# ArduinoNanoShield.net
KiCad netlist of a schematic drawn in Altium Designer
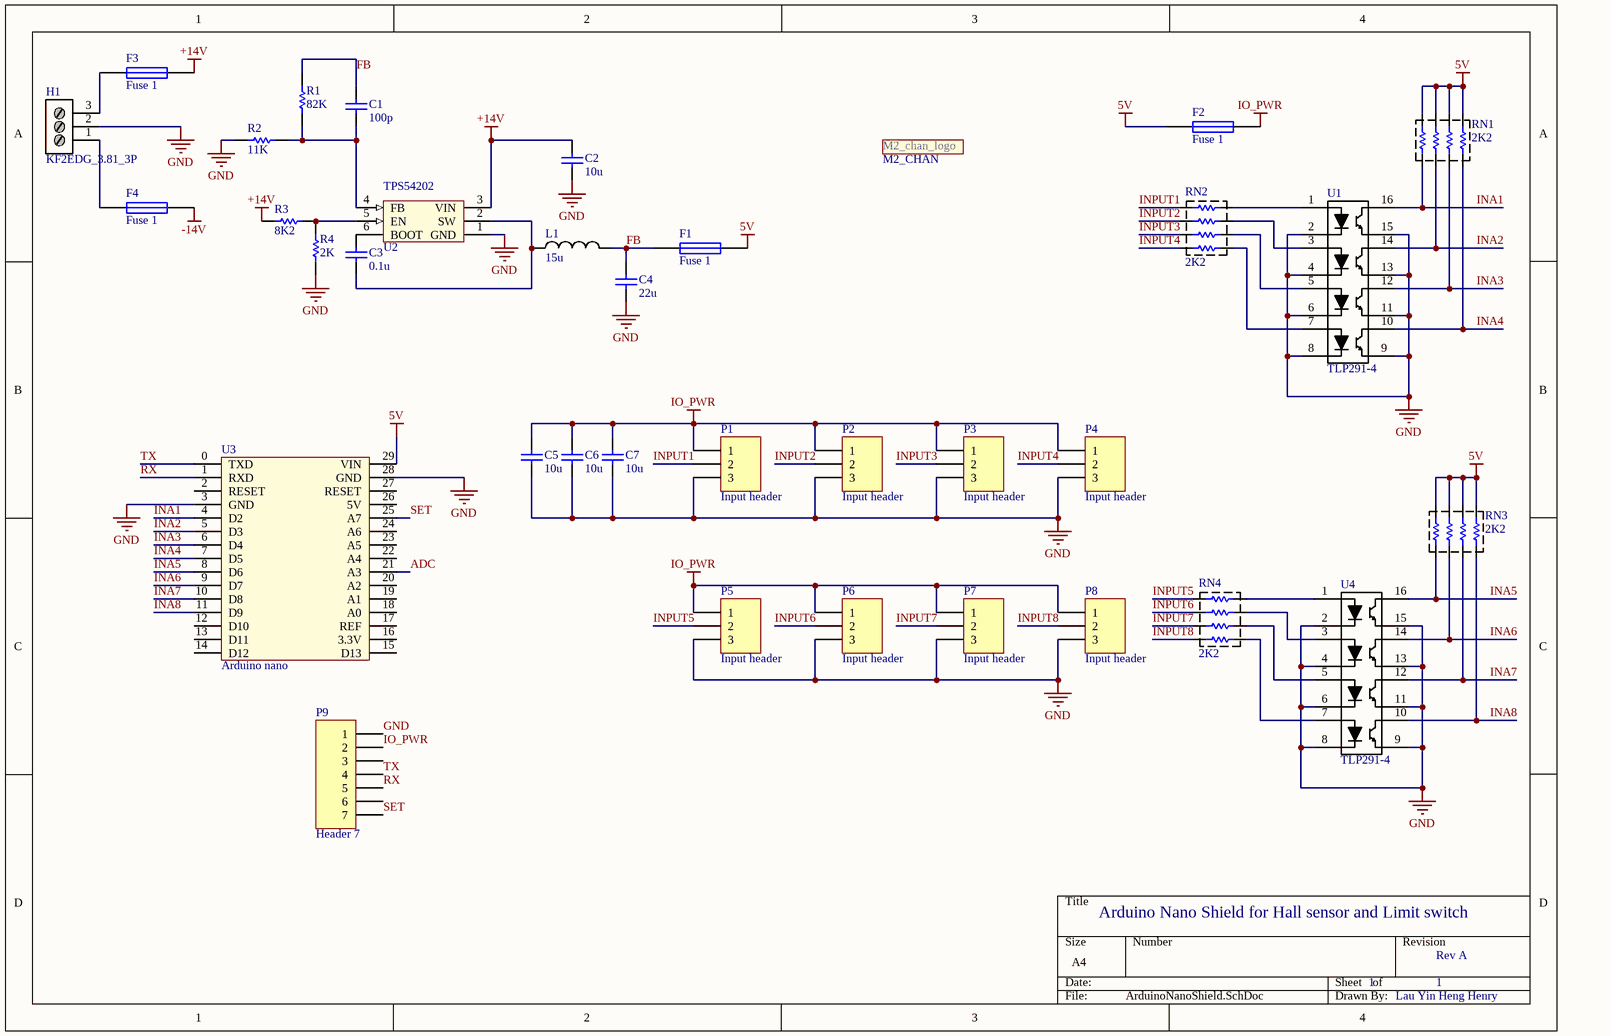
[diagram p0: ArduinoNanoShield.SchDoc]

(export (version "E")
  (design (tool "Eeschema 10.0.6"))
  (components
    (comp (ref "C1")
      (value "100p")
      (footprint "CAPC1608X90N")
      (description "Capacitor")
      (fields (field (name "Comment") "Cap") (field (name "PUBLISHER") "Altium Limited"))
      (libsource (lib "IOBoard_Low") (part "Cap"))
    )
    (comp (ref "C2")
      (value "10u")
      (footprint "CAPC2012X135N")
      (description "Capacitor")
      (fields (field (name "Comment") "Cap") (field (name "PUBLISHER") "Altium Limited"))
      (libsource (lib "IOBoard_Low") (part "Cap"))
    )
    (comp (ref "C3")
      (value "0.1u")
      (footprint "CAPC1608X90N")
      (description "Capacitor")
      (fields (field (name "Comment") "Cap") (field (name "PUBLISHER") "Altium Limited"))
      (libsource (lib "IOBoard_Low") (part "Cap"))
    )
    (comp (ref "C4")
      (value "22u")
      (footprint "CAPC2012X135N")
      (description "Capacitor")
      (fields (field (name "Comment") "Cap") (field (name "PUBLISHER") "Altium Limited"))
      (libsource (lib "IOBoard_Low") (part "Cap"))
    )
    (comp (ref "C5")
      (value "10u")
      (footprint "CAPC2012X135N")
      (description "Capacitor")
      (fields (field (name "Comment") "Cap") (field (name "PUBLISHER") "Altium Limited"))
      (libsource (lib "IOBoard_Low") (part "Cap"))
    )
    (comp (ref "C6")
      (value "10u")
      (footprint "CAPC2012X135N")
      (description "Capacitor")
      (fields (field (name "Comment") "Cap") (field (name "PUBLISHER") "Altium Limited"))
      (libsource (lib "IOBoard_Low") (part "Cap"))
    )
    (comp (ref "C7")
      (value "10u")
      (footprint "CAPC2012X135N")
      (description "Capacitor")
      (fields (field (name "Comment") "Cap") (field (name "PUBLISHER") "Altium Limited"))
      (libsource (lib "IOBoard_Low") (part "Cap"))
    )
    (comp (ref "F1")
      (value "Fuse 1")
      (footprint "FUSE_1808")
      (description "Fuse")
      (fields (field (name "PUBLISHER") "Altium Limited"))
      (libsource (lib "Miscellaneous Devices") (part "Fuse 1"))
    )
    (comp (ref "F2")
      (value "Fuse 1")
      (footprint "FUSE_1808")
      (description "Fuse")
      (fields (field (name "PUBLISHER") "Altium Limited"))
      (libsource (lib "Miscellaneous Devices") (part "Fuse 1"))
    )
    (comp (ref "F3")
      (value "Fuse 1")
      (footprint "FUSE_1808")
      (description "Fuse")
      (fields (field (name "PUBLISHER") "Altium Limited"))
      (libsource (lib "Miscellaneous Devices") (part "Fuse 1"))
    )
    (comp (ref "F4")
      (value "Fuse 1")
      (footprint "FUSE_1808")
      (description "Fuse")
      (fields (field (name "PUBLISHER") "Altium Limited"))
      (libsource (lib "Miscellaneous Devices") (part "Fuse 1"))
    )
    (comp (ref "H1")
      (value "KF2EDG_3.81_3P")
      (footprint "KF2EDG_3.81_RA_3P")
      (description "KF2EDG_3.81_3P screw terminal connect, must be mount at the edge of the PCB")
      (libsource (lib "IOBoard_Low") (part "KF2EDG_3.81_3P"))
    )
    (comp (ref "L1")
      (value "15u")
      (footprint "INDC_5.5x5.3x3")
      (description "15uH inductor with 2A saturation current. Dimension is 5.5 * 5.2 * 3 mm^3")
      (fields (field (name "Comment") "15uH inductor"))
      (libsource (lib "IOBoard_Low") (part "INDC_MPX1D0530L150"))
    )
    (comp (ref "M2_CHAN")
      (value "M2_CHAN")
      (footprint "M2_chan_thin")
      (libsource (lib "IOBoard_Low") (part "M2_CHAN"))
    )
    (comp (ref "P1")
      (value "Input header")
      (footprint "HDR1X3")
      (description "Header, 3-Pin")
      (fields (field (name "PUBLISHER") "Altium Limited"))
      (libsource (lib "Miscellaneous Connectors") (part "Header 3"))
    )
    (comp (ref "P2")
      (value "Input header")
      (footprint "HDR1X3")
      (description "Header, 3-Pin")
      (fields (field (name "PUBLISHER") "Altium Limited"))
      (libsource (lib "Miscellaneous Connectors") (part "Header 3"))
    )
    (comp (ref "P3")
      (value "Input header")
      (footprint "HDR1X3")
      (description "Header, 3-Pin")
      (fields (field (name "PUBLISHER") "Altium Limited"))
      (libsource (lib "Miscellaneous Connectors") (part "Header 3"))
    )
    (comp (ref "P4")
      (value "Input header")
      (footprint "HDR1X3")
      (description "Header, 3-Pin")
      (fields (field (name "PUBLISHER") "Altium Limited"))
      (libsource (lib "Miscellaneous Connectors") (part "Header 3"))
    )
    (comp (ref "P5")
      (value "Input header")
      (footprint "HDR1X3")
      (description "Header, 3-Pin")
      (fields (field (name "PUBLISHER") "Altium Limited"))
      (libsource (lib "Miscellaneous Connectors") (part "Header 3"))
    )
    (comp (ref "P6")
      (value "Input header")
      (footprint "HDR1X3")
      (description "Header, 3-Pin")
      (fields (field (name "PUBLISHER") "Altium Limited"))
      (libsource (lib "Miscellaneous Connectors") (part "Header 3"))
    )
    (comp (ref "P7")
      (value "Input header")
      (footprint "HDR1X3")
      (description "Header, 3-Pin")
      (fields (field (name "PUBLISHER") "Altium Limited"))
      (libsource (lib "Miscellaneous Connectors") (part "Header 3"))
    )
    (comp (ref "P8")
      (value "Input header")
      (footprint "HDR1X3")
      (description "Header, 3-Pin")
      (fields (field (name "PUBLISHER") "Altium Limited"))
      (libsource (lib "Miscellaneous Connectors") (part "Header 3"))
    )
    (comp (ref "P9")
      (value "Header 7")
      (footprint "HDR1X7")
      (description "Header, 7-Pin")
      (fields (field (name "PUBLISHER") "Altium Limited"))
      (libsource (lib "Miscellaneous Connectors") (part "Header 7"))
    )
    (comp (ref "R1")
      (value "82K")
      (footprint "RESC1608X55N")
      (description "Resistor")
      (fields (field (name "Comment") "Res1") (field (name "PUBLISHER") "Altium Limited"))
      (libsource (lib "IOBoard_Low") (part "Res1"))
    )
    (comp (ref "R2")
      (value "11K")
      (footprint "RESC1608X55N")
      (description "Resistor")
      (fields (field (name "Comment") "Res1") (field (name "PUBLISHER") "Altium Limited"))
      (libsource (lib "IOBoard_Low") (part "Res1"))
    )
    (comp (ref "R3")
      (value "8K2")
      (footprint "RESC1608X55N")
      (description "Resistor")
      (fields (field (name "Comment") "Res1") (field (name "PUBLISHER") "Altium Limited"))
      (libsource (lib "IOBoard_Low") (part "Res1"))
    )
    (comp (ref "R4")
      (value "2K")
      (footprint "RESC1608X55N")
      (description "Resistor")
      (fields (field (name "Comment") "Res1") (field (name "PUBLISHER") "Altium Limited"))
      (libsource (lib "IOBoard_Low") (part "Res1"))
    )
    (comp (ref "RN1")
      (value "2K2")
      (footprint "RESCAXS50P160X320X70-8N")
      (fields (field (name "Comment") "resistor network"))
      (libsource (lib "IOBoard") (part "RES_NET"))
    )
    (comp (ref "RN2")
      (value "2K2")
      (footprint "RESCAXS50P160X320X70-8N")
      (fields (field (name "Comment") "resistor network"))
      (libsource (lib "IOBoard") (part "RES_NET"))
    )
    (comp (ref "RN3")
      (value "2K2")
      (footprint "RESCAXS50P160X320X70-8N")
      (fields (field (name "Comment") "resistor network"))
      (libsource (lib "IOBoard") (part "RES_NET"))
    )
    (comp (ref "RN4")
      (value "2K2")
      (footprint "RESCAXS50P160X320X70-8N")
      (fields (field (name "Comment") "resistor network"))
      (libsource (lib "IOBoard") (part "RES_NET"))
    )
    (comp (ref "U1") (value "TLP291-4") (footprint "SO16") (libsource (lib "IOBoard_Low") (part "TLP291-4")))
    (comp (ref "U2")
      (value "TPS54202")
      (footprint "SOT23-6")
      (description "4.5-28V input 2A output step down, EMI Friendly Synchronous Step Down Converter")
      (libsource (lib "IOBoard_Low") (part "TPS54202"))
    )
    (comp (ref "U3")
      (value "Arduino nano")
      (footprint "Arduino_Nano")
      (description "Arduino nano shield pin out")
      (libsource (lib "IOBoard") (part "ArduinoNano"))
    )
    (comp (ref "U4") (value "TLP291-4") (footprint "SO16") (libsource (lib "IOBoard_Low") (part "TLP291-4")))
  )
  (nets
    (net (code "1") (name "+14V") (class "Default")
      (node (ref "C2") (pin "1") (pinfunction "1_1") (pintype "passive"))
      (node (ref "F3") (pin "2") (pinfunction "2_2") (pintype "passive"))
      (node (ref "R3") (pin "1") (pinfunction "1_1") (pintype "passive"))
      (node (ref "U2") (pin "3") (pinfunction "VIN_3") (pintype "power_in"))
    )
    (net (code "2") (name "-14V") (class "Default")
      (node (ref "F4") (pin "2") (pinfunction "2_2") (pintype "passive"))
    )
    (net (code "3") (name "/ADC") (class "Default")
      (node (ref "U3") (pin "21") (pinfunction "A3_21") (pintype "passive"))
    )
    (net (code "4") (name "/FB") (class "Default")
      (node (ref "C1") (pin "2") (pinfunction "2_2") (pintype "passive"))
      (node (ref "C4") (pin "2") (pinfunction "2_2") (pintype "passive"))
      (node (ref "F1") (pin "1") (pinfunction "1_1") (pintype "passive"))
      (node (ref "L1") (pin "2") (pinfunction "2_2") (pintype "passive"))
      (node (ref "R1") (pin "2") (pinfunction "2_2") (pintype "passive"))
    )
    (net (code "5") (name "/INA1") (class "Default")
      (node (ref "RN1") (pin "1") (pinfunction "1_1") (pintype "power_in"))
      (node (ref "U1") (pin "16") (pinfunction "16_16") (pintype "passive"))
      (node (ref "U3") (pin "4") (pinfunction "D2_4") (pintype "passive"))
    )
    (net (code "6") (name "/INA2") (class "Default")
      (node (ref "RN1") (pin "2") (pinfunction "2_2") (pintype "power_in"))
      (node (ref "U1") (pin "14") (pinfunction "14_14") (pintype "passive"))
      (node (ref "U3") (pin "5") (pinfunction "D3_5") (pintype "passive"))
    )
    (net (code "7") (name "/INA3") (class "Default")
      (node (ref "RN1") (pin "3") (pinfunction "3_3") (pintype "power_in"))
      (node (ref "U1") (pin "12") (pinfunction "12_12") (pintype "passive"))
      (node (ref "U3") (pin "6") (pinfunction "D4_6") (pintype "passive"))
    )
    (net (code "8") (name "/INA4") (class "Default")
      (node (ref "RN1") (pin "4") (pinfunction "4_4") (pintype "power_in"))
      (node (ref "U1") (pin "10") (pinfunction "10_10") (pintype "passive"))
      (node (ref "U3") (pin "7") (pinfunction "D5_7") (pintype "passive"))
    )
    (net (code "9") (name "/INA5") (class "Default")
      (node (ref "RN3") (pin "1") (pinfunction "1_1") (pintype "power_in"))
      (node (ref "U3") (pin "8") (pinfunction "D6_8") (pintype "passive"))
      (node (ref "U4") (pin "16") (pinfunction "16_16") (pintype "passive"))
    )
    (net (code "10") (name "/INA6") (class "Default")
      (node (ref "RN3") (pin "2") (pinfunction "2_2") (pintype "power_in"))
      (node (ref "U3") (pin "9") (pinfunction "D7_9") (pintype "passive"))
      (node (ref "U4") (pin "14") (pinfunction "14_14") (pintype "passive"))
    )
    (net (code "11") (name "/INA7") (class "Default")
      (node (ref "RN3") (pin "3") (pinfunction "3_3") (pintype "power_in"))
      (node (ref "U3") (pin "10") (pinfunction "D8_10") (pintype "passive"))
      (node (ref "U4") (pin "12") (pinfunction "12_12") (pintype "passive"))
    )
    (net (code "12") (name "/INA8") (class "Default")
      (node (ref "RN3") (pin "4") (pinfunction "4_4") (pintype "power_in"))
      (node (ref "U3") (pin "11") (pinfunction "D9_11") (pintype "passive"))
      (node (ref "U4") (pin "10") (pinfunction "10_10") (pintype "passive"))
    )
    (net (code "13") (name "/INPUT1") (class "Default")
      (node (ref "P1") (pin "2") (pinfunction "2_2") (pintype "passive"))
      (node (ref "RN2") (pin "5") (pinfunction "5_5") (pintype "power_in"))
    )
    (net (code "14") (name "/INPUT2") (class "Default")
      (node (ref "P2") (pin "2") (pinfunction "2_2") (pintype "passive"))
      (node (ref "RN2") (pin "6") (pinfunction "6_6") (pintype "power_in"))
    )
    (net (code "15") (name "/INPUT3") (class "Default")
      (node (ref "P3") (pin "2") (pinfunction "2_2") (pintype "passive"))
      (node (ref "RN2") (pin "7") (pinfunction "7_7") (pintype "power_in"))
    )
    (net (code "16") (name "/INPUT4") (class "Default")
      (node (ref "P4") (pin "2") (pinfunction "2_2") (pintype "passive"))
      (node (ref "RN2") (pin "8") (pinfunction "8_8") (pintype "power_in"))
    )
    (net (code "17") (name "/INPUT5") (class "Default")
      (node (ref "P5") (pin "2") (pinfunction "2_2") (pintype "passive"))
      (node (ref "RN4") (pin "5") (pinfunction "5_5") (pintype "power_in"))
    )
    (net (code "18") (name "/INPUT6") (class "Default")
      (node (ref "P6") (pin "2") (pinfunction "2_2") (pintype "passive"))
      (node (ref "RN4") (pin "6") (pinfunction "6_6") (pintype "power_in"))
    )
    (net (code "19") (name "/INPUT7") (class "Default")
      (node (ref "P7") (pin "2") (pinfunction "2_2") (pintype "passive"))
      (node (ref "RN4") (pin "7") (pinfunction "7_7") (pintype "power_in"))
    )
    (net (code "20") (name "/INPUT8") (class "Default")
      (node (ref "P8") (pin "2") (pinfunction "2_2") (pintype "passive"))
      (node (ref "RN4") (pin "8") (pinfunction "8_8") (pintype "power_in"))
    )
    (net (code "21") (name "/RX") (class "Default")
      (node (ref "P9") (pin "5") (pinfunction "5_5") (pintype "passive"))
      (node (ref "U3") (pin "1") (pinfunction "RXD_1") (pintype "passive"))
    )
    (net (code "22") (name "/SET") (class "Default")
      (node (ref "P9") (pin "7") (pinfunction "7_7") (pintype "passive"))
      (node (ref "U3") (pin "25") (pinfunction "A7_25") (pintype "passive"))
    )
    (net (code "23") (name "/TX") (class "Default")
      (node (ref "P9") (pin "4") (pinfunction "4_4") (pintype "passive"))
      (node (ref "U3") (pin "0") (pinfunction "TXD_0") (pintype "passive"))
    )
    (net (code "24") (name "5V") (class "Default")
      (node (ref "F1") (pin "2") (pinfunction "2_2") (pintype "passive"))
      (node (ref "F2") (pin "1") (pinfunction "1_1") (pintype "passive"))
      (node (ref "RN1") (pin "5") (pinfunction "5_5") (pintype "power_in"))
      (node (ref "RN1") (pin "6") (pinfunction "6_6") (pintype "power_in"))
      (node (ref "RN1") (pin "7") (pinfunction "7_7") (pintype "power_in"))
      (node (ref "RN1") (pin "8") (pinfunction "8_8") (pintype "power_in"))
      (node (ref "RN3") (pin "5") (pinfunction "5_5") (pintype "power_in"))
      (node (ref "RN3") (pin "6") (pinfunction "6_6") (pintype "power_in"))
      (node (ref "RN3") (pin "7") (pinfunction "7_7") (pintype "power_in"))
      (node (ref "RN3") (pin "8") (pinfunction "8_8") (pintype "power_in"))
      (node (ref "U3") (pin "29") (pinfunction "VIN_29") (pintype "passive"))
    )
    (net (code "25") (name "GND") (class "Default")
      (node (ref "C2") (pin "2") (pinfunction "2_2") (pintype "passive"))
      (node (ref "C4") (pin "1") (pinfunction "1_1") (pintype "passive"))
      (node (ref "C5") (pin "2") (pinfunction "2_2") (pintype "passive"))
      (node (ref "C6") (pin "2") (pinfunction "2_2") (pintype "passive"))
      (node (ref "C7") (pin "2") (pinfunction "2_2") (pintype "passive"))
      (node (ref "H1") (pin "2") (pinfunction "2_2") (pintype "power_in"))
      (node (ref "P1") (pin "3") (pinfunction "3_3") (pintype "passive"))
      (node (ref "P2") (pin "3") (pinfunction "3_3") (pintype "passive"))
      (node (ref "P3") (pin "3") (pinfunction "3_3") (pintype "passive"))
      (node (ref "P4") (pin "3") (pinfunction "3_3") (pintype "passive"))
      (node (ref "P5") (pin "3") (pinfunction "3_3") (pintype "passive"))
      (node (ref "P6") (pin "3") (pinfunction "3_3") (pintype "passive"))
      (node (ref "P7") (pin "3") (pinfunction "3_3") (pintype "passive"))
      (node (ref "P8") (pin "3") (pinfunction "3_3") (pintype "passive"))
      (node (ref "P9") (pin "1") (pinfunction "1_1") (pintype "passive"))
      (node (ref "R2") (pin "2") (pinfunction "2_2") (pintype "passive"))
      (node (ref "R4") (pin "1") (pinfunction "1_1") (pintype "passive"))
      (node (ref "U1") (pin "11") (pinfunction "11_11") (pintype "passive"))
      (node (ref "U1") (pin "13") (pinfunction "13_13") (pintype "passive"))
      (node (ref "U1") (pin "15") (pinfunction "15_15") (pintype "passive"))
      (node (ref "U1") (pin "2") (pinfunction "2_2") (pintype "passive"))
      (node (ref "U1") (pin "4") (pinfunction "4_4") (pintype "passive"))
      (node (ref "U1") (pin "6") (pinfunction "6_6") (pintype "passive"))
      (node (ref "U1") (pin "8") (pinfunction "8_8") (pintype "passive"))
      (node (ref "U1") (pin "9") (pinfunction "9_9") (pintype "passive"))
      (node (ref "U2") (pin "1") (pinfunction "GND_1") (pintype "power_in"))
      (node (ref "U3") (pin "28") (pinfunction "GND_28") (pintype "passive"))
      (node (ref "U3") (pin "3") (pinfunction "GND_3") (pintype "passive"))
      (node (ref "U4") (pin "11") (pinfunction "11_11") (pintype "passive"))
      (node (ref "U4") (pin "13") (pinfunction "13_13") (pintype "passive"))
      (node (ref "U4") (pin "15") (pinfunction "15_15") (pintype "passive"))
      (node (ref "U4") (pin "2") (pinfunction "2_2") (pintype "passive"))
      (node (ref "U4") (pin "4") (pinfunction "4_4") (pintype "passive"))
      (node (ref "U4") (pin "6") (pinfunction "6_6") (pintype "passive"))
      (node (ref "U4") (pin "8") (pinfunction "8_8") (pintype "passive"))
      (node (ref "U4") (pin "9") (pinfunction "9_9") (pintype "passive"))
    )
    (net (code "26") (name "IO_PWR") (class "Default")
      (node (ref "C5") (pin "1") (pinfunction "1_1") (pintype "passive"))
      (node (ref "C6") (pin "1") (pinfunction "1_1") (pintype "passive"))
      (node (ref "C7") (pin "1") (pinfunction "1_1") (pintype "passive"))
      (node (ref "F2") (pin "2") (pinfunction "2_2") (pintype "passive"))
      (node (ref "P1") (pin "1") (pinfunction "1_1") (pintype "passive"))
      (node (ref "P2") (pin "1") (pinfunction "1_1") (pintype "passive"))
      (node (ref "P3") (pin "1") (pinfunction "1_1") (pintype "passive"))
      (node (ref "P4") (pin "1") (pinfunction "1_1") (pintype "passive"))
      (node (ref "P5") (pin "1") (pinfunction "1_1") (pintype "passive"))
      (node (ref "P6") (pin "1") (pinfunction "1_1") (pintype "passive"))
      (node (ref "P7") (pin "1") (pinfunction "1_1") (pintype "passive"))
      (node (ref "P8") (pin "1") (pinfunction "1_1") (pintype "passive"))
      (node (ref "P9") (pin "2") (pinfunction "2_2") (pintype "passive"))
    )
    (net (code "27") (name "Net-(F3-Pad1)") (class "Default")
      (node (ref "F3") (pin "1") (pinfunction "1_1") (pintype "passive"))
      (node (ref "H1") (pin "3") (pinfunction "3_3") (pintype "passive"))
    )
    (net (code "28") (name "Net-(F4-Pad1)") (class "Default")
      (node (ref "F4") (pin "1") (pinfunction "1_1") (pintype "passive"))
      (node (ref "H1") (pin "1") (pinfunction "1_1") (pintype "passive"))
    )
    (net (code "29") (name "Net-(RN2-Pad1)") (class "Default")
      (node (ref "RN2") (pin "1") (pinfunction "1_1") (pintype "power_in"))
      (node (ref "U1") (pin "7") (pinfunction "7_7") (pintype "passive"))
    )
    (net (code "30") (name "Net-(RN2-Pad2)") (class "Default")
      (node (ref "RN2") (pin "2") (pinfunction "2_2") (pintype "power_in"))
      (node (ref "U1") (pin "5") (pinfunction "5_5") (pintype "passive"))
    )
    (net (code "31") (name "Net-(RN2-Pad3)") (class "Default")
      (node (ref "RN2") (pin "3") (pinfunction "3_3") (pintype "power_in"))
      (node (ref "U1") (pin "3") (pinfunction "3_3") (pintype "passive"))
    )
    (net (code "32") (name "Net-(RN2-Pad4)") (class "Default")
      (node (ref "RN2") (pin "4") (pinfunction "4_4") (pintype "power_in"))
      (node (ref "U1") (pin "1") (pinfunction "1_1") (pintype "passive"))
    )
    (net (code "33") (name "Net-(RN4-Pad1)") (class "Default")
      (node (ref "RN4") (pin "1") (pinfunction "1_1") (pintype "power_in"))
      (node (ref "U4") (pin "7") (pinfunction "7_7") (pintype "passive"))
    )
    (net (code "34") (name "Net-(RN4-Pad2)") (class "Default")
      (node (ref "RN4") (pin "2") (pinfunction "2_2") (pintype "power_in"))
      (node (ref "U4") (pin "5") (pinfunction "5_5") (pintype "passive"))
    )
    (net (code "35") (name "Net-(RN4-Pad3)") (class "Default")
      (node (ref "RN4") (pin "3") (pinfunction "3_3") (pintype "power_in"))
      (node (ref "U4") (pin "3") (pinfunction "3_3") (pintype "passive"))
    )
    (net (code "36") (name "Net-(RN4-Pad4)") (class "Default")
      (node (ref "RN4") (pin "4") (pinfunction "4_4") (pintype "power_in"))
      (node (ref "U4") (pin "1") (pinfunction "1_1") (pintype "passive"))
    )
    (net (code "37") (name "Net-(U2-BOOT)") (class "Default")
      (node (ref "C3") (pin "2") (pinfunction "2_2") (pintype "passive"))
      (node (ref "U2") (pin "6") (pinfunction "BOOT_6") (pintype "passive"))
    )
    (net (code "38") (name "Net-(U2-EN)") (class "Default")
      (node (ref "R3") (pin "2") (pinfunction "2_2") (pintype "passive"))
      (node (ref "R4") (pin "2") (pinfunction "2_2") (pintype "passive"))
      (node (ref "U2") (pin "5") (pinfunction "EN_5") (pintype "input"))
    )
    (net (code "39") (name "Net-(U2-FB)") (class "Default")
      (node (ref "C1") (pin "1") (pinfunction "1_1") (pintype "passive"))
      (node (ref "R1") (pin "1") (pinfunction "1_1") (pintype "passive"))
      (node (ref "R2") (pin "1") (pinfunction "1_1") (pintype "passive"))
      (node (ref "U2") (pin "4") (pinfunction "FB_4") (pintype "input"))
    )
    (net (code "40") (name "Net-(U2-SW)") (class "Default")
      (node (ref "C3") (pin "1") (pinfunction "1_1") (pintype "passive"))
      (node (ref "L1") (pin "1") (pinfunction "1_1") (pintype "passive"))
      (node (ref "U2") (pin "2") (pinfunction "SW_2") (pintype "power_in"))
    )
    (net (code "41") (name "unconnected-(P9-Pad3)") (class "Default")
      (node (ref "P9") (pin "3") (pinfunction "3_3") (pintype "passive"))
    )
    (net (code "42") (name "unconnected-(P9-Pad6)") (class "Default")
      (node (ref "P9") (pin "6") (pinfunction "6_6") (pintype "passive"))
    )
    (net (code "43") (name "unconnected-(U3-3.3V-Pad16)") (class "Default")
      (node (ref "U3") (pin "16") (pinfunction "3.3V_16") (pintype "passive"))
    )
    (net (code "44") (name "unconnected-(U3-5V-Pad26)") (class "Default")
      (node (ref "U3") (pin "26") (pinfunction "5V_26") (pintype "passive"))
    )
    (net (code "45") (name "unconnected-(U3-A0-Pad18)") (class "Default")
      (node (ref "U3") (pin "18") (pinfunction "A0_18") (pintype "passive"))
    )
    (net (code "46") (name "unconnected-(U3-A1-Pad19)") (class "Default")
      (node (ref "U3") (pin "19") (pinfunction "A1_19") (pintype "passive"))
    )
    (net (code "47") (name "unconnected-(U3-A2-Pad20)") (class "Default")
      (node (ref "U3") (pin "20") (pinfunction "A2_20") (pintype "passive"))
    )
    (net (code "48") (name "unconnected-(U3-A4-Pad22)") (class "Default")
      (node (ref "U3") (pin "22") (pinfunction "A4_22") (pintype "passive"))
    )
    (net (code "49") (name "unconnected-(U3-A5-Pad23)") (class "Default")
      (node (ref "U3") (pin "23") (pinfunction "A5_23") (pintype "passive"))
    )
    (net (code "50") (name "unconnected-(U3-A6-Pad24)") (class "Default")
      (node (ref "U3") (pin "24") (pinfunction "A6_24") (pintype "passive"))
    )
    (net (code "51") (name "unconnected-(U3-D10-Pad12)") (class "Default")
      (node (ref "U3") (pin "12") (pinfunction "D10_12") (pintype "passive"))
    )
    (net (code "52") (name "unconnected-(U3-D11-Pad13)") (class "Default")
      (node (ref "U3") (pin "13") (pinfunction "D11_13") (pintype "passive"))
    )
    (net (code "53") (name "unconnected-(U3-D12-Pad14)") (class "Default")
      (node (ref "U3") (pin "14") (pinfunction "D12_14") (pintype "passive"))
    )
    (net (code "54") (name "unconnected-(U3-D13-Pad15)") (class "Default")
      (node (ref "U3") (pin "15") (pinfunction "D13_15") (pintype "passive"))
    )
    (net (code "55") (name "unconnected-(U3-REF-Pad17)") (class "Default")
      (node (ref "U3") (pin "17") (pinfunction "REF_17") (pintype "passive"))
    )
    (net (code "56") (name "unconnected-(U3-RESET-Pad2)") (class "Default")
      (node (ref "U3") (pin "2") (pinfunction "RESET_2") (pintype "passive"))
    )
    (net (code "57") (name "unconnected-(U3-RESET-Pad27)") (class "Default")
      (node (ref "U3") (pin "27") (pinfunction "RESET_27") (pintype "passive"))
    )
  )
)
